# LowCurrentIO.net
KiCad netlist of a schematic drawn in Altium Designer
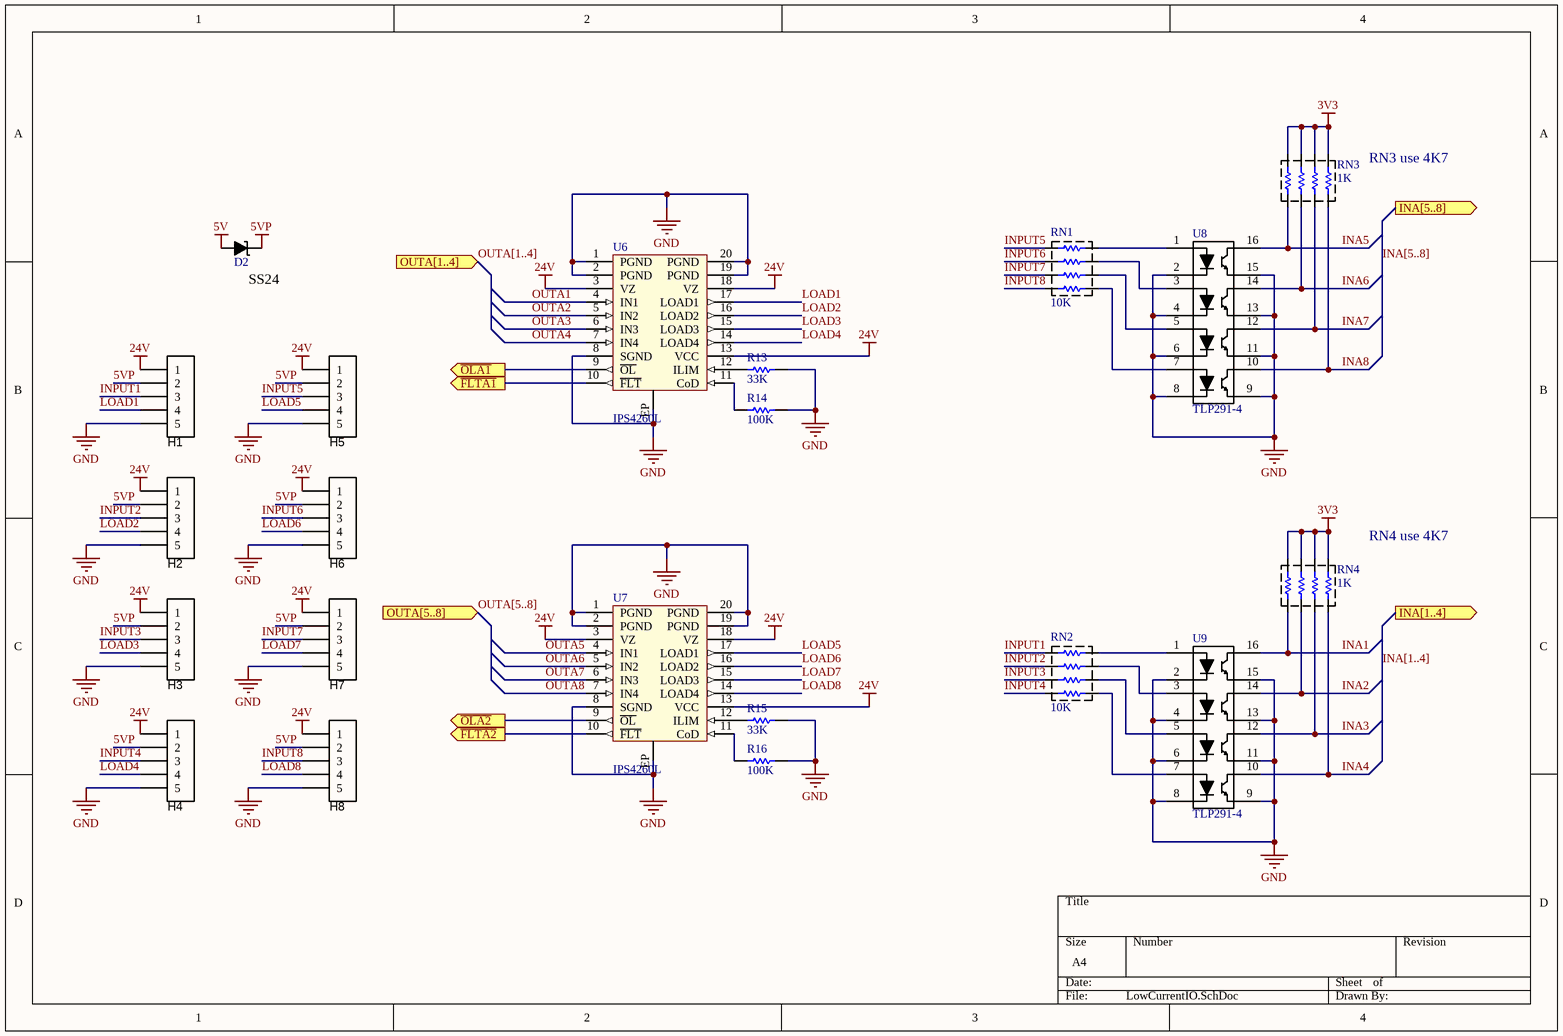
[diagram p0: LowCurrentIO.SchDoc]

(export (version "E")
  (design (tool "Eeschema 10.0.6"))
  (components
    (comp (ref "D2")
      (value "MBRA210LT3G")
      (footprint "SMA")
      (description "Surface Mount  Schottky Power Rectifier")
      (fields (field (name "MANUFACTURER") "ON semiconductor"))
      (libsource (lib "IOBoard_Low") (part "MBRA210LT3G"))
    )
    (comp (ref "H1")
      (value "Programmer")
      (footprint "HDR_1X5_2.54MM _TE_CONC")
      (description "Header 5-pin")
      (libsource (lib "IOBoard_Low") (part "Header5P"))
    )
    (comp (ref "H2")
      (value "Programmer")
      (footprint "HDR_1X5_2.54MM _TE_CONC")
      (description "Header 5-pin")
      (libsource (lib "IOBoard_Low") (part "Header5P"))
    )
    (comp (ref "H3")
      (value "Programmer")
      (footprint "HDR_1X5_2.54MM _TE_CONC")
      (description "Header 5-pin")
      (libsource (lib "IOBoard_Low") (part "Header5P"))
    )
    (comp (ref "H4")
      (value "Programmer")
      (footprint "HDR_1X5_2.54MM _TE_CONC")
      (description "Header 5-pin")
      (libsource (lib "IOBoard_Low") (part "Header5P"))
    )
    (comp (ref "H5")
      (value "Programmer")
      (footprint "HDR_1X5_2.54MM _TE_CONC")
      (description "Header 5-pin")
      (libsource (lib "IOBoard_Low") (part "Header5P"))
    )
    (comp (ref "H6")
      (value "Programmer")
      (footprint "HDR_1X5_2.54MM _TE_CONC")
      (description "Header 5-pin")
      (libsource (lib "IOBoard_Low") (part "Header5P"))
    )
    (comp (ref "H7")
      (value "Programmer")
      (footprint "HDR_1X5_2.54MM _TE_CONC")
      (description "Header 5-pin")
      (libsource (lib "IOBoard_Low") (part "Header5P"))
    )
    (comp (ref "H8")
      (value "Programmer")
      (footprint "HDR_1X5_2.54MM _TE_CONC")
      (description "Header 5-pin")
      (libsource (lib "IOBoard_Low") (part "Header5P"))
    )
    (comp (ref "R13")
      (value "33K")
      (footprint "RESC1608X55N")
      (description "Resistor")
      (fields (field (name "Comment") "Res1") (field (name "PUBLISHER") "Altium Limited"))
      (libsource (lib "IOBoard_Low") (part "Res1"))
    )
    (comp (ref "R14")
      (value "100K")
      (footprint "RESC1608X55N")
      (description "Resistor")
      (fields (field (name "Comment") "Res1") (field (name "PUBLISHER") "Altium Limited"))
      (libsource (lib "IOBoard_Low") (part "Res1"))
    )
    (comp (ref "R15")
      (value "33K")
      (footprint "RESC1608X55N")
      (description "Resistor")
      (fields (field (name "Comment") "Res1") (field (name "PUBLISHER") "Altium Limited"))
      (libsource (lib "IOBoard_Low") (part "Res1"))
    )
    (comp (ref "R16")
      (value "100K")
      (footprint "RESC1608X55N")
      (description "Resistor")
      (fields (field (name "Comment") "Res1") (field (name "PUBLISHER") "Altium Limited"))
      (libsource (lib "IOBoard_Low") (part "Res1"))
    )
    (comp (ref "RN1")
      (value "10K")
      (footprint "RESCAXS50P160X320X70-8N")
      (fields (field (name "Comment") "resistor network"))
      (libsource (lib "IOBoard") (part "RES_NET"))
    )
    (comp (ref "RN2")
      (value "10K")
      (footprint "RESCAXS50P160X320X70-8N")
      (fields (field (name "Comment") "resistor network"))
      (libsource (lib "IOBoard") (part "RES_NET"))
    )
    (comp (ref "RN3")
      (value "1K")
      (footprint "RESCAXS50P160X320X70-8N")
      (fields (field (name "Comment") "resistor network"))
      (libsource (lib "IOBoard") (part "RES_NET"))
    )
    (comp (ref "RN4")
      (value "1K")
      (footprint "RESCAXS50P160X320X70-8N")
      (fields (field (name "Comment") "resistor network"))
      (libsource (lib "IOBoard") (part "RES_NET"))
    )
    (comp (ref "U6")
      (value "IPS4260L")
      (footprint "HTSSOP20")
      (description "IPS4260L Quad low side power switch")
      (libsource (lib "IOBoard_Low") (part "IPS4260L"))
    )
    (comp (ref "U7")
      (value "IPS4260L")
      (footprint "HTSSOP20")
      (description "IPS4260L Quad low side power switch")
      (libsource (lib "IOBoard_Low") (part "IPS4260L"))
    )
    (comp (ref "U8") (value "TLP291-4") (footprint "SOP16") (libsource (lib "IOBoard_Low") (part "TLP291-4")))
    (comp (ref "U9") (value "TLP291-4") (footprint "SOP16") (libsource (lib "IOBoard_Low") (part "TLP291-4")))
  )
  (nets
    (net (code "1") (name "/INA1") (class "Default")
      (node (ref "RN4") (pin "1") (pinfunction "1_1") (pintype "power_in"))
      (node (ref "U9") (pin "16") (pinfunction "16_16") (pintype "passive"))
    )
    (net (code "2") (name "/INA2") (class "Default")
      (node (ref "RN4") (pin "2") (pinfunction "2_2") (pintype "power_in"))
      (node (ref "U9") (pin "14") (pinfunction "14_14") (pintype "passive"))
    )
    (net (code "3") (name "/INA3") (class "Default")
      (node (ref "RN4") (pin "3") (pinfunction "3_3") (pintype "power_in"))
      (node (ref "U9") (pin "12") (pinfunction "12_12") (pintype "passive"))
    )
    (net (code "4") (name "/INA4") (class "Default")
      (node (ref "RN4") (pin "4") (pinfunction "4_4") (pintype "power_in"))
      (node (ref "U9") (pin "10") (pinfunction "10_10") (pintype "passive"))
    )
    (net (code "5") (name "/INA5") (class "Default")
      (node (ref "RN3") (pin "1") (pinfunction "1_1") (pintype "power_in"))
      (node (ref "U8") (pin "16") (pinfunction "16_16") (pintype "passive"))
    )
    (net (code "6") (name "/INA6") (class "Default")
      (node (ref "RN3") (pin "2") (pinfunction "2_2") (pintype "power_in"))
      (node (ref "U8") (pin "14") (pinfunction "14_14") (pintype "passive"))
    )
    (net (code "7") (name "/INA7") (class "Default")
      (node (ref "RN3") (pin "3") (pinfunction "3_3") (pintype "power_in"))
      (node (ref "U8") (pin "12") (pinfunction "12_12") (pintype "passive"))
    )
    (net (code "8") (name "/INA8") (class "Default")
      (node (ref "RN3") (pin "4") (pinfunction "4_4") (pintype "power_in"))
      (node (ref "U8") (pin "10") (pinfunction "10_10") (pintype "passive"))
    )
    (net (code "11") (name "/INPUT1") (class "Default")
      (node (ref "H1") (pin "3") (pinfunction "3_3") (pintype "passive"))
      (node (ref "RN2") (pin "5") (pinfunction "5_5") (pintype "power_in"))
    )
    (net (code "12") (name "/INPUT2") (class "Default")
      (node (ref "H2") (pin "3") (pinfunction "3_3") (pintype "passive"))
      (node (ref "RN2") (pin "6") (pinfunction "6_6") (pintype "power_in"))
    )
    (net (code "13") (name "/INPUT3") (class "Default")
      (node (ref "H3") (pin "3") (pinfunction "3_3") (pintype "passive"))
      (node (ref "RN2") (pin "7") (pinfunction "7_7") (pintype "power_in"))
    )
    (net (code "14") (name "/INPUT4") (class "Default")
      (node (ref "H4") (pin "3") (pinfunction "3_3") (pintype "passive"))
      (node (ref "RN2") (pin "8") (pinfunction "8_8") (pintype "power_in"))
    )
    (net (code "15") (name "/INPUT5") (class "Default")
      (node (ref "H5") (pin "3") (pinfunction "3_3") (pintype "passive"))
      (node (ref "RN1") (pin "5") (pinfunction "5_5") (pintype "power_in"))
    )
    (net (code "16") (name "/INPUT6") (class "Default")
      (node (ref "H6") (pin "3") (pinfunction "3_3") (pintype "passive"))
      (node (ref "RN1") (pin "6") (pinfunction "6_6") (pintype "power_in"))
    )
    (net (code "17") (name "/INPUT7") (class "Default")
      (node (ref "H7") (pin "3") (pinfunction "3_3") (pintype "passive"))
      (node (ref "RN1") (pin "7") (pinfunction "7_7") (pintype "power_in"))
    )
    (net (code "18") (name "/INPUT8") (class "Default")
      (node (ref "H8") (pin "3") (pinfunction "3_3") (pintype "passive"))
      (node (ref "RN1") (pin "8") (pinfunction "8_8") (pintype "power_in"))
    )
    (net (code "19") (name "/LOAD1") (class "Default")
      (node (ref "H1") (pin "4") (pinfunction "4_4") (pintype "passive"))
      (node (ref "U6") (pin "17") (pinfunction "LOAD1_17") (pintype "output"))
    )
    (net (code "20") (name "/LOAD2") (class "Default")
      (node (ref "H2") (pin "4") (pinfunction "4_4") (pintype "passive"))
      (node (ref "U6") (pin "16") (pinfunction "LOAD2_16") (pintype "output"))
    )
    (net (code "21") (name "/LOAD3") (class "Default")
      (node (ref "H3") (pin "4") (pinfunction "4_4") (pintype "passive"))
      (node (ref "U6") (pin "15") (pinfunction "LOAD3_15") (pintype "output"))
    )
    (net (code "22") (name "/LOAD4") (class "Default")
      (node (ref "H4") (pin "4") (pinfunction "4_4") (pintype "passive"))
      (node (ref "U6") (pin "14") (pinfunction "LOAD4_14") (pintype "output"))
    )
    (net (code "23") (name "/LOAD5") (class "Default")
      (node (ref "H5") (pin "4") (pinfunction "4_4") (pintype "passive"))
      (node (ref "U7") (pin "17") (pinfunction "LOAD1_17") (pintype "output"))
    )
    (net (code "24") (name "/LOAD6") (class "Default")
      (node (ref "H6") (pin "4") (pinfunction "4_4") (pintype "passive"))
      (node (ref "U7") (pin "16") (pinfunction "LOAD2_16") (pintype "output"))
    )
    (net (code "25") (name "/LOAD7") (class "Default")
      (node (ref "H7") (pin "4") (pinfunction "4_4") (pintype "passive"))
      (node (ref "U7") (pin "15") (pinfunction "LOAD3_15") (pintype "output"))
    )
    (net (code "26") (name "/LOAD8") (class "Default")
      (node (ref "H8") (pin "4") (pinfunction "4_4") (pintype "passive"))
      (node (ref "U7") (pin "14") (pinfunction "LOAD4_14") (pintype "output"))
    )
    (net (code "27") (name "/OUTA1") (class "Default")
      (node (ref "U6") (pin "4") (pinfunction "IN1_4") (pintype "input"))
    )
    (net (code "28") (name "/OUTA2") (class "Default")
      (node (ref "U6") (pin "5") (pinfunction "IN2_5") (pintype "input"))
    )
    (net (code "29") (name "/OUTA3") (class "Default")
      (node (ref "U6") (pin "6") (pinfunction "IN3_6") (pintype "input"))
    )
    (net (code "30") (name "/OUTA4") (class "Default")
      (node (ref "U6") (pin "7") (pinfunction "IN4_7") (pintype "input"))
    )
    (net (code "31") (name "/OUTA5") (class "Default")
      (node (ref "U7") (pin "4") (pinfunction "IN1_4") (pintype "input"))
    )
    (net (code "32") (name "/OUTA6") (class "Default")
      (node (ref "U7") (pin "5") (pinfunction "IN2_5") (pintype "input"))
    )
    (net (code "33") (name "/OUTA7") (class "Default")
      (node (ref "U7") (pin "6") (pinfunction "IN3_6") (pintype "input"))
    )
    (net (code "34") (name "/OUTA8") (class "Default")
      (node (ref "U7") (pin "7") (pinfunction "IN4_7") (pintype "input"))
    )
    (net (code "37") (name "/~{FLTA1}") (class "Default")
      (node (ref "U6") (pin "10") (pinfunction "~{FLT}_10") (pintype "output"))
    )
    (net (code "38") (name "/~{FLTA2}") (class "Default")
      (node (ref "U7") (pin "10") (pinfunction "~{FLT}_10") (pintype "output"))
    )
    (net (code "39") (name "/~{OLA1}") (class "Default")
      (node (ref "U6") (pin "9") (pinfunction "~{OL}_9") (pintype "output"))
    )
    (net (code "40") (name "/~{OLA2}") (class "Default")
      (node (ref "U7") (pin "9") (pinfunction "~{OL}_9") (pintype "output"))
    )
    (net (code "41") (name "3V3") (class "Default")
      (node (ref "RN3") (pin "5") (pinfunction "5_5") (pintype "power_in"))
      (node (ref "RN3") (pin "6") (pinfunction "6_6") (pintype "power_in"))
      (node (ref "RN3") (pin "7") (pinfunction "7_7") (pintype "power_in"))
      (node (ref "RN3") (pin "8") (pinfunction "8_8") (pintype "power_in"))
      (node (ref "RN4") (pin "5") (pinfunction "5_5") (pintype "power_in"))
      (node (ref "RN4") (pin "6") (pinfunction "6_6") (pintype "power_in"))
      (node (ref "RN4") (pin "7") (pinfunction "7_7") (pintype "power_in"))
      (node (ref "RN4") (pin "8") (pinfunction "8_8") (pintype "power_in"))
    )
    (net (code "42") (name "5V") (class "Default")
      (node (ref "D2") (pin "A") (pinfunction "Anode_A") (pintype "passive"))
    )
    (net (code "43") (name "5VP") (class "Default")
      (node (ref "D2") (pin "K") (pinfunction "Cathode_K") (pintype "passive"))
      (node (ref "H1") (pin "2") (pinfunction "2_2") (pintype "passive"))
      (node (ref "H2") (pin "2") (pinfunction "2_2") (pintype "passive"))
      (node (ref "H3") (pin "2") (pinfunction "2_2") (pintype "passive"))
      (node (ref "H4") (pin "2") (pinfunction "2_2") (pintype "passive"))
      (node (ref "H5") (pin "2") (pinfunction "2_2") (pintype "passive"))
      (node (ref "H6") (pin "2") (pinfunction "2_2") (pintype "passive"))
      (node (ref "H7") (pin "2") (pinfunction "2_2") (pintype "passive"))
      (node (ref "H8") (pin "2") (pinfunction "2_2") (pintype "passive"))
    )
    (net (code "44") (name "24V") (class "Default")
      (node (ref "H1") (pin "1") (pinfunction "1_1") (pintype "passive"))
      (node (ref "H2") (pin "1") (pinfunction "1_1") (pintype "passive"))
      (node (ref "H3") (pin "1") (pinfunction "1_1") (pintype "passive"))
      (node (ref "H4") (pin "1") (pinfunction "1_1") (pintype "passive"))
      (node (ref "H5") (pin "1") (pinfunction "1_1") (pintype "passive"))
      (node (ref "H6") (pin "1") (pinfunction "1_1") (pintype "passive"))
      (node (ref "H7") (pin "1") (pinfunction "1_1") (pintype "passive"))
      (node (ref "H8") (pin "1") (pinfunction "1_1") (pintype "passive"))
      (node (ref "U6") (pin "13") (pinfunction "VCC_13") (pintype "power_in"))
      (node (ref "U6") (pin "18") (pinfunction "VZ_18") (pintype "power_in"))
      (node (ref "U6") (pin "3") (pinfunction "VZ_3") (pintype "power_in"))
      (node (ref "U7") (pin "13") (pinfunction "VCC_13") (pintype "power_in"))
      (node (ref "U7") (pin "18") (pinfunction "VZ_18") (pintype "power_in"))
      (node (ref "U7") (pin "3") (pinfunction "VZ_3") (pintype "power_in"))
    )
    (net (code "45") (name "GND") (class "Default")
      (node (ref "H1") (pin "5") (pinfunction "5_5") (pintype "passive"))
      (node (ref "H2") (pin "5") (pinfunction "5_5") (pintype "passive"))
      (node (ref "H3") (pin "5") (pinfunction "5_5") (pintype "passive"))
      (node (ref "H4") (pin "5") (pinfunction "5_5") (pintype "passive"))
      (node (ref "H5") (pin "5") (pinfunction "5_5") (pintype "passive"))
      (node (ref "H6") (pin "5") (pinfunction "5_5") (pintype "passive"))
      (node (ref "H7") (pin "5") (pinfunction "5_5") (pintype "passive"))
      (node (ref "H8") (pin "5") (pinfunction "5_5") (pintype "passive"))
      (node (ref "R13") (pin "1") (pinfunction "1_1") (pintype "passive"))
      (node (ref "R14") (pin "1") (pinfunction "1_1") (pintype "passive"))
      (node (ref "R15") (pin "1") (pinfunction "1_1") (pintype "passive"))
      (node (ref "R16") (pin "1") (pinfunction "1_1") (pintype "passive"))
      (node (ref "U6") (pin "1") (pinfunction "PGND_1") (pintype "power_in"))
      (node (ref "U6") (pin "19") (pinfunction "PGND_19") (pintype "power_in"))
      (node (ref "U6") (pin "2") (pinfunction "PGND_2") (pintype "power_in"))
      (node (ref "U6") (pin "20") (pinfunction "PGND_20") (pintype "power_in"))
      (node (ref "U6") (pin "8") (pinfunction "SGND_8") (pintype "power_in"))
      (node (ref "U6") (pin "EP") (pinfunction "EP_EP") (pintype "power_in"))
      (node (ref "U7") (pin "1") (pinfunction "PGND_1") (pintype "power_in"))
      (node (ref "U7") (pin "19") (pinfunction "PGND_19") (pintype "power_in"))
      (node (ref "U7") (pin "2") (pinfunction "PGND_2") (pintype "power_in"))
      (node (ref "U7") (pin "20") (pinfunction "PGND_20") (pintype "power_in"))
      (node (ref "U7") (pin "8") (pinfunction "SGND_8") (pintype "power_in"))
      (node (ref "U7") (pin "EP") (pinfunction "EP_EP") (pintype "power_in"))
      (node (ref "U8") (pin "11") (pinfunction "11_11") (pintype "passive"))
      (node (ref "U8") (pin "13") (pinfunction "13_13") (pintype "passive"))
      (node (ref "U8") (pin "15") (pinfunction "15_15") (pintype "passive"))
      (node (ref "U8") (pin "2") (pinfunction "2_2") (pintype "passive"))
      (node (ref "U8") (pin "4") (pinfunction "4_4") (pintype "passive"))
      (node (ref "U8") (pin "6") (pinfunction "6_6") (pintype "passive"))
      (node (ref "U8") (pin "8") (pinfunction "8_8") (pintype "passive"))
      (node (ref "U8") (pin "9") (pinfunction "9_9") (pintype "passive"))
      (node (ref "U9") (pin "11") (pinfunction "11_11") (pintype "passive"))
      (node (ref "U9") (pin "13") (pinfunction "13_13") (pintype "passive"))
      (node (ref "U9") (pin "15") (pinfunction "15_15") (pintype "passive"))
      (node (ref "U9") (pin "2") (pinfunction "2_2") (pintype "passive"))
      (node (ref "U9") (pin "4") (pinfunction "4_4") (pintype "passive"))
      (node (ref "U9") (pin "6") (pinfunction "6_6") (pintype "passive"))
      (node (ref "U9") (pin "8") (pinfunction "8_8") (pintype "passive"))
      (node (ref "U9") (pin "9") (pinfunction "9_9") (pintype "passive"))
    )
    (net (code "46") (name "Net-(RN1-Pad1)") (class "Default")
      (node (ref "RN1") (pin "1") (pinfunction "1_1") (pintype "power_in"))
      (node (ref "U8") (pin "7") (pinfunction "7_7") (pintype "passive"))
    )
    (net (code "47") (name "Net-(RN1-Pad2)") (class "Default")
      (node (ref "RN1") (pin "2") (pinfunction "2_2") (pintype "power_in"))
      (node (ref "U8") (pin "5") (pinfunction "5_5") (pintype "passive"))
    )
    (net (code "48") (name "Net-(RN1-Pad3)") (class "Default")
      (node (ref "RN1") (pin "3") (pinfunction "3_3") (pintype "power_in"))
      (node (ref "U8") (pin "3") (pinfunction "3_3") (pintype "passive"))
    )
    (net (code "49") (name "Net-(RN1-Pad4)") (class "Default")
      (node (ref "RN1") (pin "4") (pinfunction "4_4") (pintype "power_in"))
      (node (ref "U8") (pin "1") (pinfunction "1_1") (pintype "passive"))
    )
    (net (code "50") (name "Net-(RN2-Pad1)") (class "Default")
      (node (ref "RN2") (pin "1") (pinfunction "1_1") (pintype "power_in"))
      (node (ref "U9") (pin "7") (pinfunction "7_7") (pintype "passive"))
    )
    (net (code "51") (name "Net-(RN2-Pad2)") (class "Default")
      (node (ref "RN2") (pin "2") (pinfunction "2_2") (pintype "power_in"))
      (node (ref "U9") (pin "5") (pinfunction "5_5") (pintype "passive"))
    )
    (net (code "52") (name "Net-(RN2-Pad3)") (class "Default")
      (node (ref "RN2") (pin "3") (pinfunction "3_3") (pintype "power_in"))
      (node (ref "U9") (pin "3") (pinfunction "3_3") (pintype "passive"))
    )
    (net (code "53") (name "Net-(RN2-Pad4)") (class "Default")
      (node (ref "RN2") (pin "4") (pinfunction "4_4") (pintype "power_in"))
      (node (ref "U9") (pin "1") (pinfunction "1_1") (pintype "passive"))
    )
    (net (code "54") (name "Net-(U6-CoD)") (class "Default")
      (node (ref "R14") (pin "2") (pinfunction "2_2") (pintype "passive"))
      (node (ref "U6") (pin "11") (pinfunction "CoD_11") (pintype "input"))
    )
    (net (code "55") (name "Net-(U6-ILIM)") (class "Default")
      (node (ref "R13") (pin "2") (pinfunction "2_2") (pintype "passive"))
      (node (ref "U6") (pin "12") (pinfunction "ILIM_12") (pintype "input"))
    )
    (net (code "56") (name "Net-(U7-CoD)") (class "Default")
      (node (ref "R16") (pin "2") (pinfunction "2_2") (pintype "passive"))
      (node (ref "U7") (pin "11") (pinfunction "CoD_11") (pintype "input"))
    )
    (net (code "57") (name "Net-(U7-ILIM)") (class "Default")
      (node (ref "R15") (pin "2") (pinfunction "2_2") (pintype "passive"))
      (node (ref "U7") (pin "12") (pinfunction "ILIM_12") (pintype "input"))
    )
  )
)
